# ec16_motor_breakout.net
KiCad netlist of a schematic drawn in EAGLE
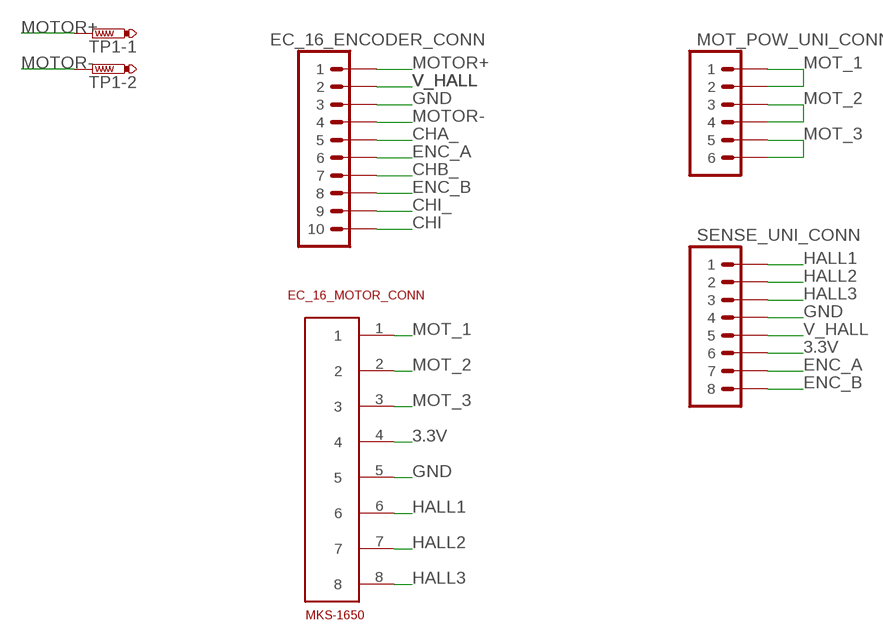
[diagram p0: schematic, sheet 1]

(export (version "E")
  (design (tool "Eeschema 10.0.6"))
  (components
    (comp (ref "EC_16_ENCODER_CONN")
      (value "CONN_RECT_2X5'_VERT")
      (footprint "eagle-import:2X5")
      (libsource (lib "eagle-import") (part "CONN_RECT_2X5'_VERT"))
    )
    (comp (ref "EC_16_MOTOR_CONN")
      (value "MKS-1650")
      (footprint "eagle-import:MKS-1650")
      (libsource (lib "eagle-import") (part "MKS-1650"))
    )
    (comp (ref "MOT_POW_UNI_CONN")
      (value "CONN_RECT_2X3_VERT")
      (footprint "eagle-import:2X3")
      (libsource (lib "eagle-import") (part "CONN_RECT_2X3_VERT"))
    )
    (comp (ref "SENSE_UNI_CONN")
      (value "CONN_RECT_2X4_")
      (footprint "eagle-import:2X4")
      (libsource (lib "eagle-import") (part "CONN_RECT_2X4_"))
    )
    (comp (ref "TP1")
      (value "PTR2")
      (footprint "eagle-import:P2-38-17")
      (libsource (lib "eagle-import") (part "PTR2"))
    )
  )
  (nets
    (net (code "1") (name "/3.3V") (class "Default")
      (node (ref "EC_16_MOTOR_CONN") (pin "4") (pinfunction "4_4") (pintype "bidirectional"))
      (node (ref "SENSE_UNI_CONN") (pin "6") (pinfunction "6_6") (pintype "passive"))
    )
    (net (code "2") (name "/CHA_") (class "Default")
      (node (ref "EC_16_ENCODER_CONN") (pin "5") (pinfunction "5_5") (pintype "passive"))
    )
    (net (code "3") (name "/CHB_") (class "Default")
      (node (ref "EC_16_ENCODER_CONN") (pin "7") (pinfunction "7_7") (pintype "passive"))
    )
    (net (code "4") (name "/CHI") (class "Default")
      (node (ref "EC_16_ENCODER_CONN") (pin "10") (pinfunction "10_10") (pintype "passive"))
    )
    (net (code "5") (name "/CHI_") (class "Default")
      (node (ref "EC_16_ENCODER_CONN") (pin "9") (pinfunction "9_9") (pintype "passive"))
    )
    (net (code "6") (name "/ENC_A") (class "Default")
      (node (ref "EC_16_ENCODER_CONN") (pin "6") (pinfunction "6_6") (pintype "passive"))
      (node (ref "SENSE_UNI_CONN") (pin "7") (pinfunction "7_7") (pintype "passive"))
    )
    (net (code "7") (name "/ENC_B") (class "Default")
      (node (ref "EC_16_ENCODER_CONN") (pin "8") (pinfunction "8_8") (pintype "passive"))
      (node (ref "SENSE_UNI_CONN") (pin "8") (pinfunction "8_8") (pintype "passive"))
    )
    (net (code "8") (name "/GND") (class "Default")
      (node (ref "EC_16_ENCODER_CONN") (pin "3") (pinfunction "3_3") (pintype "passive"))
      (node (ref "EC_16_MOTOR_CONN") (pin "5") (pinfunction "5_5") (pintype "bidirectional"))
      (node (ref "SENSE_UNI_CONN") (pin "4") (pinfunction "4_4") (pintype "passive"))
    )
    (net (code "9") (name "/HALL1") (class "Default")
      (node (ref "EC_16_MOTOR_CONN") (pin "6") (pinfunction "6_6") (pintype "bidirectional"))
      (node (ref "SENSE_UNI_CONN") (pin "1") (pinfunction "1_1") (pintype "passive"))
    )
    (net (code "10") (name "/HALL2") (class "Default")
      (node (ref "EC_16_MOTOR_CONN") (pin "7") (pinfunction "7_7") (pintype "bidirectional"))
      (node (ref "SENSE_UNI_CONN") (pin "2") (pinfunction "2_2") (pintype "passive"))
    )
    (net (code "11") (name "/HALL3") (class "Default")
      (node (ref "EC_16_MOTOR_CONN") (pin "8") (pinfunction "8_8") (pintype "bidirectional"))
      (node (ref "SENSE_UNI_CONN") (pin "3") (pinfunction "3_3") (pintype "passive"))
    )
    (net (code "12") (name "/MOTOR+") (class "Default")
      (node (ref "EC_16_ENCODER_CONN") (pin "1") (pinfunction "1_1") (pintype "passive"))
      (node (ref "TP1") (pin "TP-1") (pinfunction "TP_TP-1") (pintype "input"))
    )
    (net (code "13") (name "/MOTOR-") (class "Default")
      (node (ref "EC_16_ENCODER_CONN") (pin "4") (pinfunction "4_4") (pintype "passive"))
      (node (ref "TP1") (pin "TP-2") (pinfunction "TP_TP-2") (pintype "input"))
    )
    (net (code "14") (name "/MOT_1") (class "Default")
      (node (ref "EC_16_MOTOR_CONN") (pin "1") (pinfunction "1_1") (pintype "bidirectional"))
      (node (ref "MOT_POW_UNI_CONN") (pin "1") (pinfunction "1_1") (pintype "passive"))
      (node (ref "MOT_POW_UNI_CONN") (pin "2") (pinfunction "2_2") (pintype "passive"))
    )
    (net (code "15") (name "/MOT_2") (class "Default")
      (node (ref "EC_16_MOTOR_CONN") (pin "2") (pinfunction "2_2") (pintype "bidirectional"))
      (node (ref "MOT_POW_UNI_CONN") (pin "3") (pinfunction "3_3") (pintype "passive"))
      (node (ref "MOT_POW_UNI_CONN") (pin "4") (pinfunction "4_4") (pintype "passive"))
    )
    (net (code "16") (name "/MOT_3") (class "Default")
      (node (ref "EC_16_MOTOR_CONN") (pin "3") (pinfunction "3_3") (pintype "bidirectional"))
      (node (ref "MOT_POW_UNI_CONN") (pin "5") (pinfunction "5_5") (pintype "passive"))
      (node (ref "MOT_POW_UNI_CONN") (pin "6") (pinfunction "6_6") (pintype "passive"))
    )
    (net (code "17") (name "/V_HALL") (class "Default")
      (node (ref "EC_16_ENCODER_CONN") (pin "2") (pinfunction "2_2") (pintype "passive"))
      (node (ref "SENSE_UNI_CONN") (pin "5") (pinfunction "5_5") (pintype "passive"))
    )
  )
)
